# EXT_DC_OUT.net
KiCad netlist of a schematic drawn in EAGLE
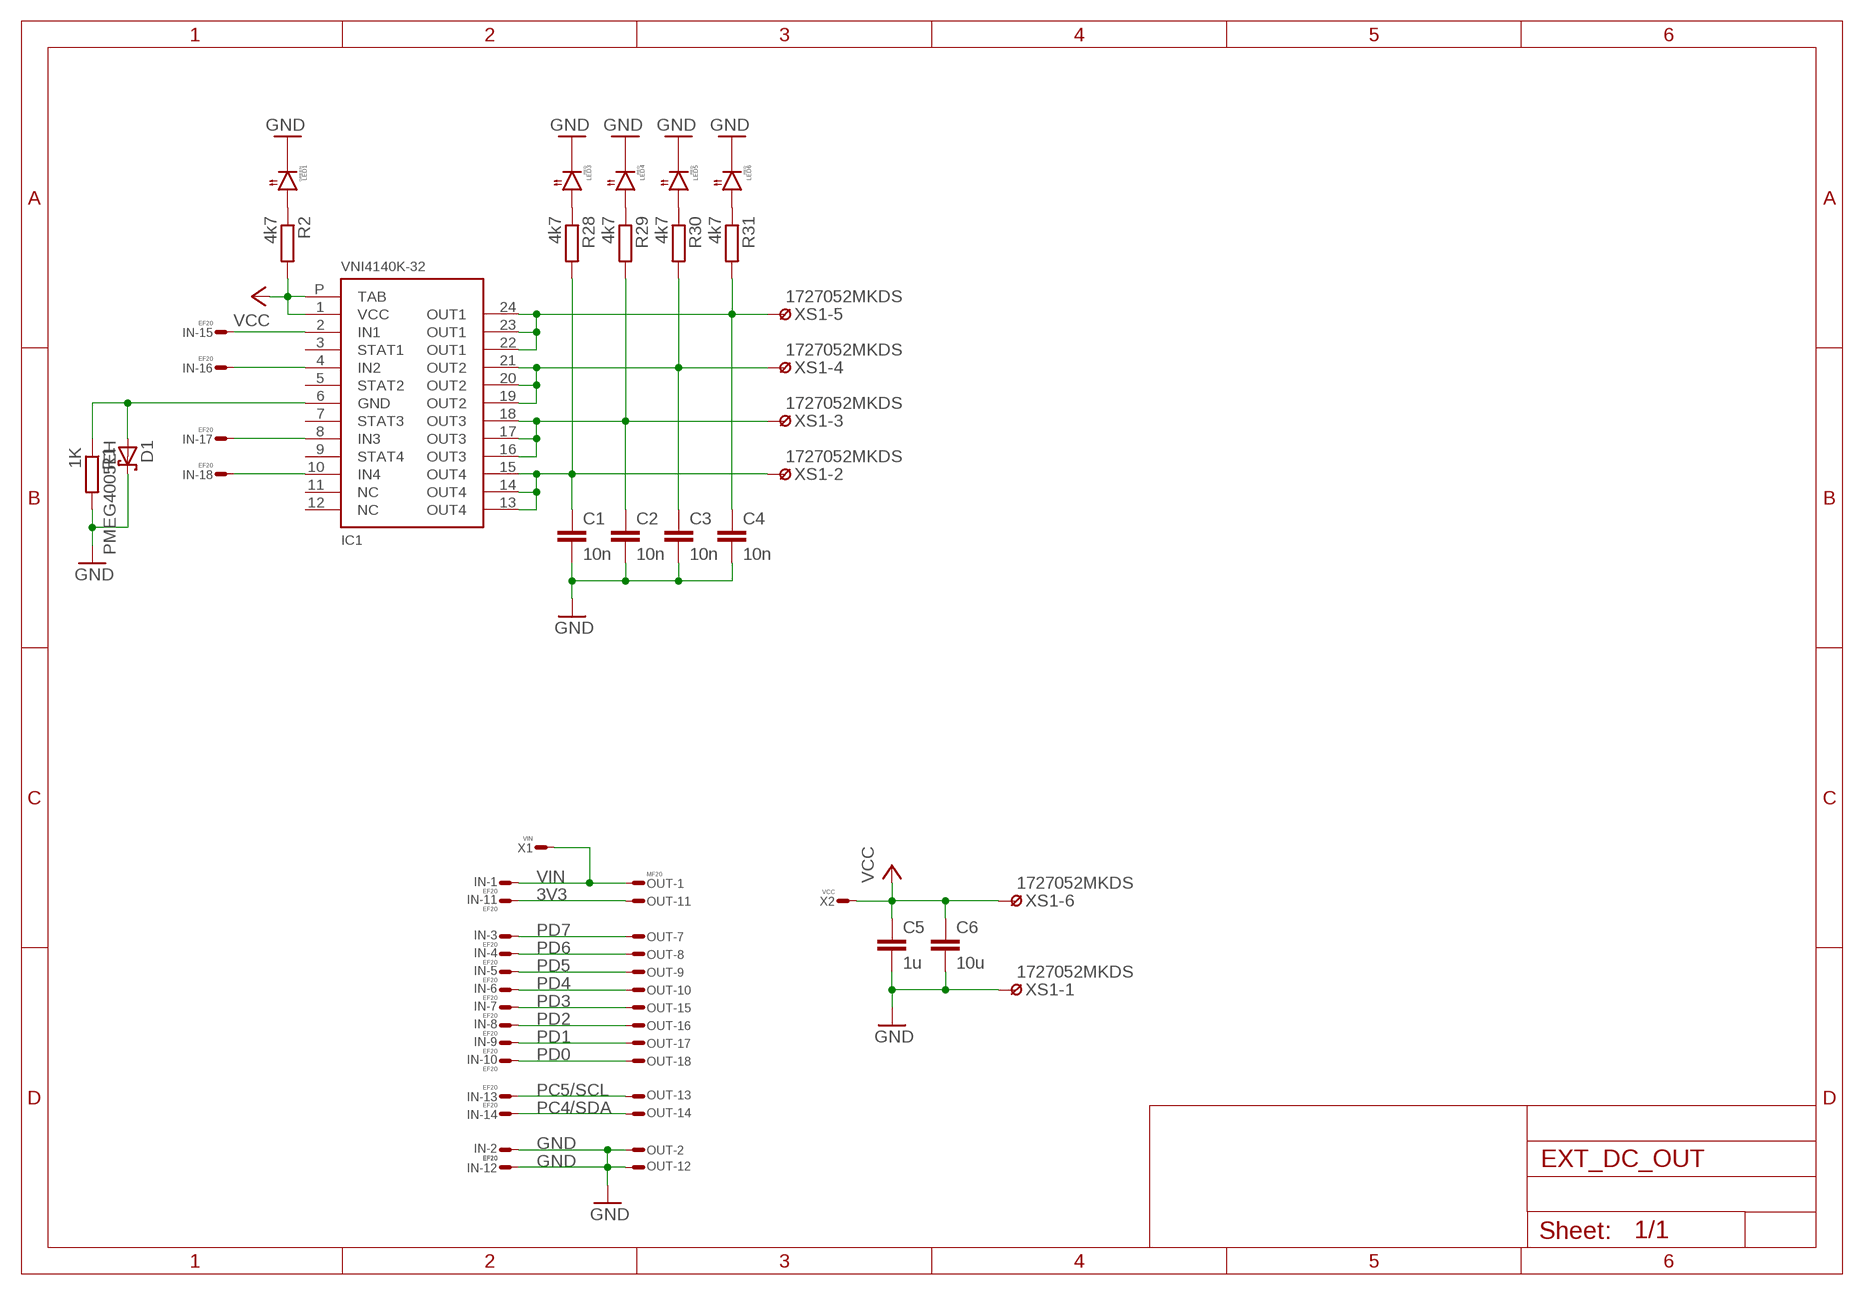
[diagram p0: schematic, sheet 1]

(export (version "E")
  (design (tool "Eeschema 10.0.6"))
  (components
    (comp (ref "C1")
      (value "10n")
      (footprint "eagle-import:1206")
      (libsource (lib "eagle-import") (part "C1206"))
    )
    (comp (ref "C2")
      (value "10n")
      (footprint "eagle-import:1206")
      (libsource (lib "eagle-import") (part "C1206"))
    )
    (comp (ref "C3")
      (value "10n")
      (footprint "eagle-import:1206")
      (libsource (lib "eagle-import") (part "C1206"))
    )
    (comp (ref "C4")
      (value "10n")
      (footprint "eagle-import:1206")
      (libsource (lib "eagle-import") (part "C1206"))
    )
    (comp (ref "C5")
      (value "1u")
      (footprint "eagle-import:1206")
      (libsource (lib "eagle-import") (part "C1206"))
    )
    (comp (ref "C6")
      (value "10u")
      (footprint "eagle-import:C1210")
      (libsource (lib "eagle-import") (part "CC1210"))
    )
    (comp (ref "D1")
      (value "PMEG4005EH")
      (footprint "eagle-import:SOD123")
      (libsource (lib "eagle-import") (part "D-SCHOTKY123"))
    )
    (comp (ref "IC1")
      (value "VNI4140K-32")
      (footprint "eagle-import:PSSO-24")
      (libsource (lib "eagle-import") (part "VNI4140"))
    )
    (comp (ref "IN")
      (value "EF20")
      (footprint "eagle-import:FE10-2WSS")
      (libsource (lib "eagle-import") (part "FE20ELSS"))
    )
    (comp (ref "LED1")
      (value "GREEN")
      (footprint "eagle-import:1206")
      (libsource (lib "eagle-import") (part "LED1206"))
    )
    (comp (ref "LED3")
      (value "RED")
      (footprint "eagle-import:1206")
      (libsource (lib "eagle-import") (part "LED1206"))
    )
    (comp (ref "LED4")
      (value "RED")
      (footprint "eagle-import:1206")
      (libsource (lib "eagle-import") (part "LED1206"))
    )
    (comp (ref "LED5")
      (value "RED")
      (footprint "eagle-import:1206")
      (libsource (lib "eagle-import") (part "LED1206"))
    )
    (comp (ref "LED6")
      (value "RED")
      (footprint "eagle-import:1206")
      (libsource (lib "eagle-import") (part "LED1206"))
    )
    (comp (ref "OUT")
      (value "MF20")
      (footprint "eagle-import:ML20LS")
      (libsource (lib "eagle-import") (part "ML20?ELS"))
    )
    (comp (ref "R1")
      (value "1K")
      (footprint "eagle-import:1206")
      (libsource (lib "eagle-import") (part "R1206"))
    )
    (comp (ref "R2")
      (value "4k7")
      (footprint "eagle-import:1206")
      (libsource (lib "eagle-import") (part "R1206"))
    )
    (comp (ref "R28")
      (value "4k7")
      (footprint "eagle-import:1206")
      (libsource (lib "eagle-import") (part "R1206"))
    )
    (comp (ref "R29")
      (value "4k7")
      (footprint "eagle-import:1206")
      (libsource (lib "eagle-import") (part "R1206"))
    )
    (comp (ref "R30")
      (value "4k7")
      (footprint "eagle-import:1206")
      (libsource (lib "eagle-import") (part "R1206"))
    )
    (comp (ref "R31")
      (value "4k7")
      (footprint "eagle-import:1206")
      (libsource (lib "eagle-import") (part "R1206"))
    )
    (comp (ref "X1")
      (value "VIN")
      (footprint "eagle-import:T1.6_0.9")
      (libsource (lib "eagle-import") (part "WIREPADT1.6/0.9"))
    )
    (comp (ref "X2")
      (value "VCC")
      (footprint "eagle-import:T1.6_0.9")
      (libsource (lib "eagle-import") (part "WIREPADT1.6/0.9"))
    )
    (comp (ref "XS1")
      (value "1727052MKDS")
      (footprint "eagle-import:1727052")
      (libsource (lib "eagle-import") (part "1727052MKDS"))
    )
  )
  (nets
    (net (code "1") (name "/3V3") (class "Default")
      (node (ref "IN") (pin "P$11") (pinfunction "S_P$11") (pintype "passive"))
      (node (ref "OUT") (pin "P$11") (pinfunction "S_P$11") (pintype "passive"))
    )
    (net (code "2") (name "/PC4{slash}SDA") (class "Default")
      (node (ref "IN") (pin "P$14") (pinfunction "S_P$14") (pintype "passive"))
      (node (ref "OUT") (pin "P$14") (pinfunction "S_P$14") (pintype "passive"))
    )
    (net (code "3") (name "/PC5{slash}SCL") (class "Default")
      (node (ref "IN") (pin "P$13") (pinfunction "S_P$13") (pintype "passive"))
      (node (ref "OUT") (pin "P$13") (pinfunction "S_P$13") (pintype "passive"))
    )
    (net (code "4") (name "/PD0") (class "Default")
      (node (ref "IN") (pin "P$10") (pinfunction "S_P$10") (pintype "passive"))
      (node (ref "OUT") (pin "P$18") (pinfunction "S_P$18") (pintype "passive"))
    )
    (net (code "5") (name "/PD1") (class "Default")
      (node (ref "IN") (pin "P$9") (pinfunction "S_P$9") (pintype "passive"))
      (node (ref "OUT") (pin "P$17") (pinfunction "S_P$17") (pintype "passive"))
    )
    (net (code "6") (name "/PD2") (class "Default")
      (node (ref "IN") (pin "P$8") (pinfunction "S_P$8") (pintype "passive"))
      (node (ref "OUT") (pin "P$16") (pinfunction "S_P$16") (pintype "passive"))
    )
    (net (code "7") (name "/PD3") (class "Default")
      (node (ref "IN") (pin "P$7") (pinfunction "S_P$7") (pintype "passive"))
      (node (ref "OUT") (pin "P$15") (pinfunction "S_P$15") (pintype "passive"))
    )
    (net (code "8") (name "/PD4") (class "Default")
      (node (ref "IN") (pin "P$6") (pinfunction "S_P$6") (pintype "passive"))
      (node (ref "OUT") (pin "P$10") (pinfunction "S_P$10") (pintype "passive"))
    )
    (net (code "9") (name "/PD5") (class "Default")
      (node (ref "IN") (pin "P$5") (pinfunction "S_P$5") (pintype "passive"))
      (node (ref "OUT") (pin "P$9") (pinfunction "S_P$9") (pintype "passive"))
    )
    (net (code "10") (name "/PD6") (class "Default")
      (node (ref "IN") (pin "P$4") (pinfunction "S_P$4") (pintype "passive"))
      (node (ref "OUT") (pin "P$8") (pinfunction "S_P$8") (pintype "passive"))
    )
    (net (code "11") (name "/PD7") (class "Default")
      (node (ref "IN") (pin "P$3") (pinfunction "S_P$3") (pintype "passive"))
      (node (ref "OUT") (pin "P$7") (pinfunction "S_P$7") (pintype "passive"))
    )
    (net (code "12") (name "/VIN") (class "Default")
      (node (ref "IN") (pin "P$1") (pinfunction "S_P$1") (pintype "passive"))
      (node (ref "OUT") (pin "P$1") (pinfunction "S_P$1") (pintype "passive"))
      (node (ref "X1") (pin "1") (pinfunction "S_1") (pintype "passive"))
    )
    (net (code "13") (name "GND") (class "Default")
      (node (ref "C1") (pin "2") (pinfunction "2_2") (pintype "passive"))
      (node (ref "C2") (pin "2") (pinfunction "2_2") (pintype "passive"))
      (node (ref "C3") (pin "2") (pinfunction "2_2") (pintype "passive"))
      (node (ref "C4") (pin "2") (pinfunction "2_2") (pintype "passive"))
      (node (ref "C5") (pin "2") (pinfunction "2_2") (pintype "passive"))
      (node (ref "C6") (pin "2") (pinfunction "2_2") (pintype "passive"))
      (node (ref "D1") (pin "C") (pinfunction "C_C") (pintype "passive"))
      (node (ref "IN") (pin "P$12") (pinfunction "S_P$12") (pintype "passive"))
      (node (ref "IN") (pin "P$2") (pinfunction "S_P$2") (pintype "passive"))
      (node (ref "LED1") (pin "2") (pinfunction "C_2") (pintype "bidirectional"))
      (node (ref "LED3") (pin "2") (pinfunction "C_2") (pintype "bidirectional"))
      (node (ref "LED4") (pin "2") (pinfunction "C_2") (pintype "bidirectional"))
      (node (ref "LED5") (pin "2") (pinfunction "C_2") (pintype "bidirectional"))
      (node (ref "LED6") (pin "2") (pinfunction "C_2") (pintype "bidirectional"))
      (node (ref "OUT") (pin "P$12") (pinfunction "S_P$12") (pintype "passive"))
      (node (ref "OUT") (pin "P$2") (pinfunction "S_P$2") (pintype "passive"))
      (node (ref "R1") (pin "2") (pinfunction "2_2") (pintype "passive"))
      (node (ref "XS1") (pin "1") (pinfunction "K_1") (pintype "passive"))
    )
    (net (code "14") (name "Net-(IC1-GND)") (class "Default")
      (node (ref "D1") (pin "A") (pinfunction "A_A") (pintype "passive"))
      (node (ref "IC1") (pin "6") (pinfunction "GND_6") (pintype "input"))
      (node (ref "R1") (pin "1") (pinfunction "1_1") (pintype "passive"))
    )
    (net (code "15") (name "Net-(IC1-IN1)") (class "Default")
      (node (ref "IC1") (pin "2") (pinfunction "IN1_2") (pintype "input"))
      (node (ref "IN") (pin "P$15") (pinfunction "S_P$15") (pintype "passive"))
    )
    (net (code "16") (name "Net-(IC1-IN2)") (class "Default")
      (node (ref "IC1") (pin "4") (pinfunction "IN2_4") (pintype "input"))
      (node (ref "IN") (pin "P$16") (pinfunction "S_P$16") (pintype "passive"))
    )
    (net (code "17") (name "Net-(IC1-IN3)") (class "Default")
      (node (ref "IC1") (pin "8") (pinfunction "IN3_8") (pintype "input"))
      (node (ref "IN") (pin "P$17") (pinfunction "S_P$17") (pintype "passive"))
    )
    (net (code "18") (name "Net-(IC1-IN4)") (class "Default")
      (node (ref "IC1") (pin "10") (pinfunction "IN4_10") (pintype "input"))
      (node (ref "IN") (pin "P$18") (pinfunction "S_P$18") (pintype "passive"))
    )
    (net (code "19") (name "Net-(LED1-A)") (class "Default")
      (node (ref "LED1") (pin "1") (pinfunction "A_1") (pintype "bidirectional"))
      (node (ref "R2") (pin "1") (pinfunction "1_1") (pintype "passive"))
    )
    (net (code "20") (name "Net-(LED3-A)") (class "Default")
      (node (ref "LED3") (pin "1") (pinfunction "A_1") (pintype "bidirectional"))
      (node (ref "R28") (pin "1") (pinfunction "1_1") (pintype "passive"))
    )
    (net (code "21") (name "Net-(LED4-A)") (class "Default")
      (node (ref "LED4") (pin "1") (pinfunction "A_1") (pintype "bidirectional"))
      (node (ref "R29") (pin "1") (pinfunction "1_1") (pintype "passive"))
    )
    (net (code "22") (name "Net-(LED5-A)") (class "Default")
      (node (ref "LED5") (pin "1") (pinfunction "A_1") (pintype "bidirectional"))
      (node (ref "R30") (pin "1") (pinfunction "1_1") (pintype "passive"))
    )
    (net (code "23") (name "Net-(LED6-A)") (class "Default")
      (node (ref "LED6") (pin "1") (pinfunction "A_1") (pintype "bidirectional"))
      (node (ref "R31") (pin "1") (pinfunction "1_1") (pintype "passive"))
    )
    (net (code "24") (name "Net-(XS1B-K)") (class "Default")
      (node (ref "C1") (pin "1") (pinfunction "1_1") (pintype "passive"))
      (node (ref "IC1") (pin "13") (pinfunction "OUT4_13") (pintype "tri_state"))
      (node (ref "IC1") (pin "14") (pinfunction "OUT4_14") (pintype "tri_state"))
      (node (ref "IC1") (pin "15") (pinfunction "OUT4_15") (pintype "tri_state"))
      (node (ref "R28") (pin "2") (pinfunction "2_2") (pintype "passive"))
      (node (ref "XS1") (pin "2") (pinfunction "K_2") (pintype "passive"))
    )
    (net (code "25") (name "Net-(XS1C-K)") (class "Default")
      (node (ref "C2") (pin "1") (pinfunction "1_1") (pintype "passive"))
      (node (ref "IC1") (pin "16") (pinfunction "OUT3_16") (pintype "tri_state"))
      (node (ref "IC1") (pin "17") (pinfunction "OUT3_17") (pintype "tri_state"))
      (node (ref "IC1") (pin "18") (pinfunction "OUT3_18") (pintype "tri_state"))
      (node (ref "R29") (pin "2") (pinfunction "2_2") (pintype "passive"))
      (node (ref "XS1") (pin "3") (pinfunction "K_3") (pintype "passive"))
    )
    (net (code "26") (name "Net-(XS1D-K)") (class "Default")
      (node (ref "C3") (pin "1") (pinfunction "1_1") (pintype "passive"))
      (node (ref "IC1") (pin "19") (pinfunction "OUT2_19") (pintype "tri_state"))
      (node (ref "IC1") (pin "20") (pinfunction "OUT2_20") (pintype "tri_state"))
      (node (ref "IC1") (pin "21") (pinfunction "OUT2_21") (pintype "tri_state"))
      (node (ref "R30") (pin "2") (pinfunction "2_2") (pintype "passive"))
      (node (ref "XS1") (pin "4") (pinfunction "K_4") (pintype "passive"))
    )
    (net (code "27") (name "Net-(XS1E-K)") (class "Default")
      (node (ref "C4") (pin "1") (pinfunction "1_1") (pintype "passive"))
      (node (ref "IC1") (pin "22") (pinfunction "OUT1_22") (pintype "tri_state"))
      (node (ref "IC1") (pin "23") (pinfunction "OUT1_23") (pintype "tri_state"))
      (node (ref "IC1") (pin "24") (pinfunction "OUT1_24") (pintype "tri_state"))
      (node (ref "R31") (pin "2") (pinfunction "2_2") (pintype "passive"))
      (node (ref "XS1") (pin "5") (pinfunction "K_5") (pintype "passive"))
    )
    (net (code "28") (name "VCC") (class "Default")
      (node (ref "C5") (pin "1") (pinfunction "1_1") (pintype "passive"))
      (node (ref "C6") (pin "1") (pinfunction "1_1") (pintype "passive"))
      (node (ref "IC1") (pin "1") (pinfunction "VCC_1") (pintype "input"))
      (node (ref "IC1") (pin "P") (pinfunction "TAB_P") (pintype "input"))
      (node (ref "R2") (pin "2") (pinfunction "2_2") (pintype "passive"))
      (node (ref "X2") (pin "1") (pinfunction "S_1") (pintype "passive"))
      (node (ref "XS1") (pin "6") (pinfunction "K_6") (pintype "passive"))
    )
    (net (code "29") (name "unconnected-(IC1-NC-Pad11)") (class "Default")
      (node (ref "IC1") (pin "11") (pinfunction "NC_11") (pintype "no_connect"))
    )
    (net (code "30") (name "unconnected-(IC1-NC-Pad12)") (class "Default")
      (node (ref "IC1") (pin "12") (pinfunction "NC_12") (pintype "no_connect"))
    )
    (net (code "31") (name "unconnected-(IC1-STAT1-Pad3)") (class "Default")
      (node (ref "IC1") (pin "3") (pinfunction "STAT1_3") (pintype "output"))
    )
    (net (code "32") (name "unconnected-(IC1-STAT2-Pad5)") (class "Default")
      (node (ref "IC1") (pin "5") (pinfunction "STAT2_5") (pintype "output"))
    )
    (net (code "33") (name "unconnected-(IC1-STAT3-Pad7)") (class "Default")
      (node (ref "IC1") (pin "7") (pinfunction "STAT3_7") (pintype "output"))
    )
    (net (code "34") (name "unconnected-(IC1-STAT4-Pad9)") (class "Default")
      (node (ref "IC1") (pin "9") (pinfunction "STAT4_9") (pintype "output"))
    )
  )
)
